# Dynamixel_AX_adaptor.net
KiCad netlist of a schematic drawn in Altium Designer
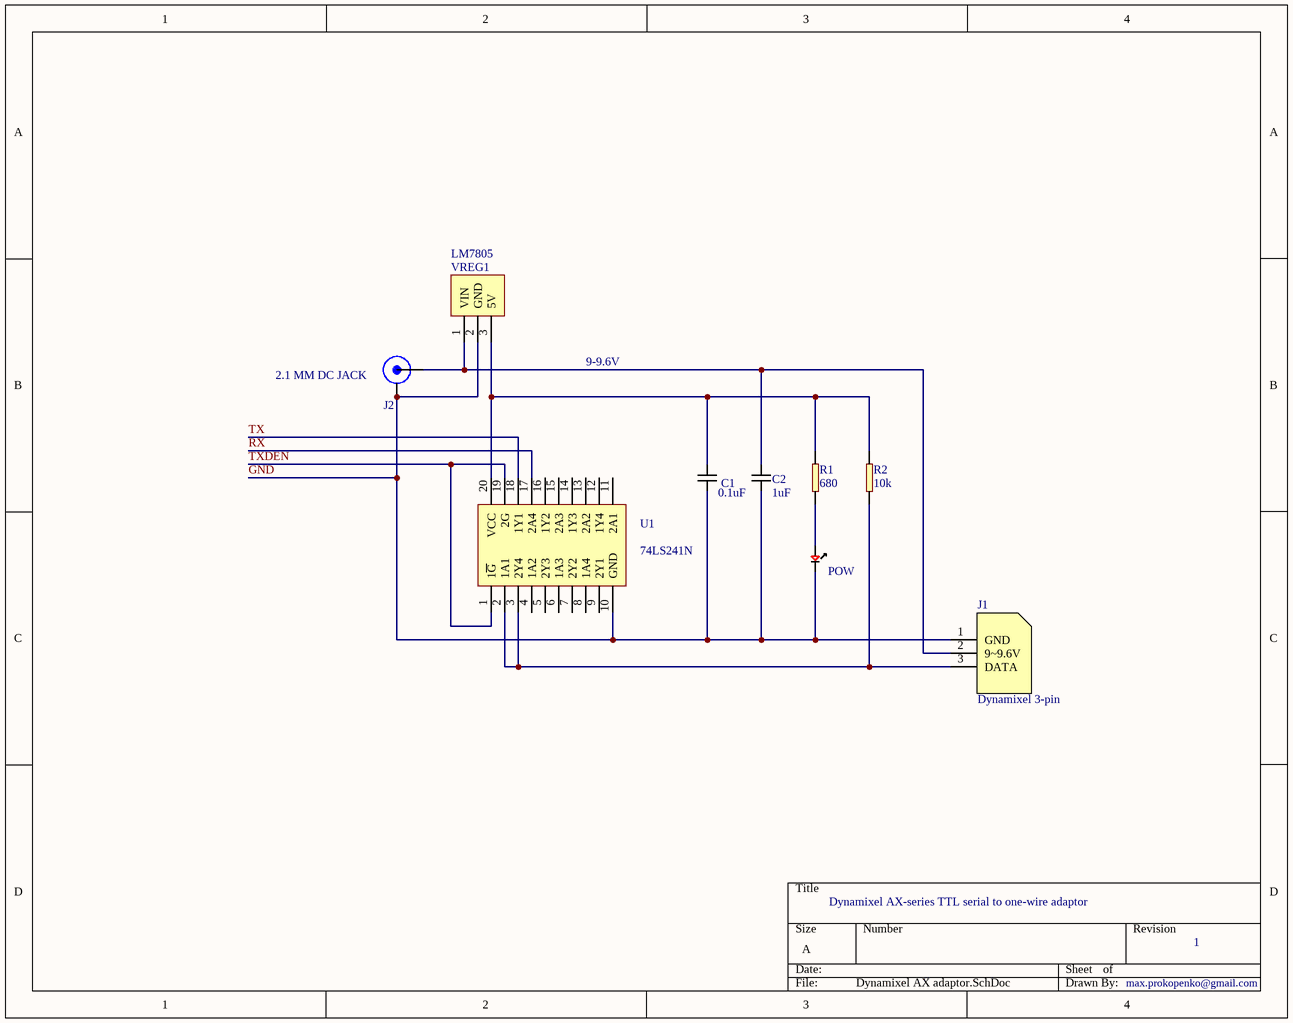
[diagram p0: Dynamixel AX adaptor.SchDoc]

(export (version "E")
  (design (tool "Eeschema 10.0.6"))
  (components
    (comp (ref "C1")
      (value "C 0.1uF 25V")
      (footprint "0603")
      (fields (field (name "C") "0.1uF"))
      (libsource (lib "RLC") (part "C 0.1uF 25V"))
    )
    (comp (ref "C2")
      (value "C 1uF 25V")
      (footprint "0603")
      (fields (field (name "C") "1uF"))
      (libsource (lib "RLC") (part "C 1uF 25V"))
    )
    (comp (ref "J1")
      (value "Dynamixel 3-pin")
      (footprint "DYNAMIXEL 3-PIN")
      (libsource (lib "OpBots") (part "Dynamixel 3-pin"))
    )
    (comp (ref "J2")
      (value "2.1 MM DC JACK")
      (footprint "DC JACK 2.1MM SMT")
      (fields (field (name "VIN") "9-9.6V"))
      (libsource (lib "OpBots") (part "SMT 2.1MM DC JACK"))
    )
    (comp (ref "POW") (value "LEDG") (footprint "0805 - LED") (libsource (lib "OpBots") (part "LEDG")))
    (comp (ref "R1")
      (value "R 680")
      (footprint "0603")
      (fields (field (name "R") "680"))
      (libsource (lib "RLC") (part "R 680"))
    )
    (comp (ref "R2")
      (value "R 10k")
      (footprint "0603")
      (fields (field (name "R") "10k"))
      (libsource (lib "RLC") (part "R 10k"))
    )
    (comp (ref "U1") (value "74LS241N") (libsource (lib "OpBots") (part "74LS241N")))
    (comp (ref "VREG1") (value "LM7805") (libsource (lib "OpBots") (part "LM7805")))
  )
  (nets
    (net (code "1") (name "/GND") (class "Default")
      (node (ref "C1") (pin "2") (pintype "passive"))
      (node (ref "C2") (pin "2") (pintype "passive"))
      (node (ref "J1") (pin "1") (pinfunction "GND_1") (pintype "passive"))
      (node (ref "J2") (pin "2") (pinfunction "G_2") (pintype "passive"))
      (node (ref "POW") (pin "2") (pinfunction "K_2") (pintype "passive"))
      (node (ref "U1") (pin "10") (pinfunction "GND_10") (pintype "passive"))
      (node (ref "VREG1") (pin "2") (pinfunction "GND_2") (pintype "passive"))
    )
    (net (code "2") (name "/RX") (class "Default")
      (node (ref "U1") (pin "17") (pinfunction "2A4_17") (pintype "passive"))
    )
    (net (code "3") (name "/TX") (class "Default")
      (node (ref "U1") (pin "18") (pinfunction "1Y1_18") (pintype "passive"))
    )
    (net (code "4") (name "/TXDEN") (class "Default")
      (node (ref "U1") (pin "1") (pinfunction "1~{G}_1") (pintype "passive"))
      (node (ref "U1") (pin "19") (pinfunction "2G_19") (pintype "passive"))
    )
    (net (code "5") (name "Net-(J1-9~9.6V)") (class "Default")
      (node (ref "C2") (pin "1") (pintype "passive"))
      (node (ref "J1") (pin "2") (pinfunction "9~9.6V_2") (pintype "passive"))
      (node (ref "J2") (pin "1") (pinfunction "S_1") (pintype "passive"))
      (node (ref "VREG1") (pin "1") (pinfunction "VIN_1") (pintype "passive"))
    )
    (net (code "6") (name "Net-(J1-DATA)") (class "Default")
      (node (ref "J1") (pin "3") (pinfunction "DATA_3") (pintype "passive"))
      (node (ref "R2") (pin "2") (pintype "passive"))
      (node (ref "U1") (pin "2") (pinfunction "1A1_2") (pintype "passive"))
      (node (ref "U1") (pin "3") (pinfunction "2Y4_3") (pintype "passive"))
    )
    (net (code "7") (name "Net-(POW-A)") (class "Default")
      (node (ref "POW") (pin "1") (pinfunction "A_1") (pintype "passive"))
      (node (ref "R1") (pin "2") (pintype "passive"))
    )
    (net (code "8") (name "Net-(U1-VCC)") (class "Default")
      (node (ref "C1") (pin "1") (pintype "passive"))
      (node (ref "R1") (pin "1") (pintype "passive"))
      (node (ref "R2") (pin "1") (pintype "passive"))
      (node (ref "U1") (pin "20") (pinfunction "VCC_20") (pintype "passive"))
      (node (ref "VREG1") (pin "3") (pinfunction "5V_3") (pintype "passive"))
    )
    (net (code "9") (name "unconnected-(U1-1A2-Pad4)") (class "Default")
      (node (ref "U1") (pin "4") (pinfunction "1A2_4") (pintype "passive"))
    )
    (net (code "10") (name "unconnected-(U1-1A3-Pad6)") (class "Default")
      (node (ref "U1") (pin "6") (pinfunction "1A3_6") (pintype "passive"))
    )
    (net (code "11") (name "unconnected-(U1-1A4-Pad8)") (class "Default")
      (node (ref "U1") (pin "8") (pinfunction "1A4_8") (pintype "passive"))
    )
    (net (code "12") (name "unconnected-(U1-1Y2-Pad16)") (class "Default")
      (node (ref "U1") (pin "16") (pinfunction "1Y2_16") (pintype "passive"))
    )
    (net (code "13") (name "unconnected-(U1-1Y3-Pad14)") (class "Default")
      (node (ref "U1") (pin "14") (pinfunction "1Y3_14") (pintype "passive"))
    )
    (net (code "14") (name "unconnected-(U1-1Y4-Pad12)") (class "Default")
      (node (ref "U1") (pin "12") (pinfunction "1Y4_12") (pintype "passive"))
    )
    (net (code "15") (name "unconnected-(U1-2A1-Pad11)") (class "Default")
      (node (ref "U1") (pin "11") (pinfunction "2A1_11") (pintype "passive"))
    )
    (net (code "16") (name "unconnected-(U1-2A2-Pad13)") (class "Default")
      (node (ref "U1") (pin "13") (pinfunction "2A2_13") (pintype "passive"))
    )
    (net (code "17") (name "unconnected-(U1-2A3-Pad15)") (class "Default")
      (node (ref "U1") (pin "15") (pinfunction "2A3_15") (pintype "passive"))
    )
    (net (code "18") (name "unconnected-(U1-2Y1-Pad9)") (class "Default")
      (node (ref "U1") (pin "9") (pinfunction "2Y1_9") (pintype "passive"))
    )
    (net (code "19") (name "unconnected-(U1-2Y2-Pad7)") (class "Default")
      (node (ref "U1") (pin "7") (pinfunction "2Y2_7") (pintype "passive"))
    )
    (net (code "20") (name "unconnected-(U1-2Y3-Pad5)") (class "Default")
      (node (ref "U1") (pin "5") (pinfunction "2Y3_5") (pintype "passive"))
    )
  )
)
